# SDC_Latch_HS.net
KiCad netlist of a schematic drawn in Altium Designer
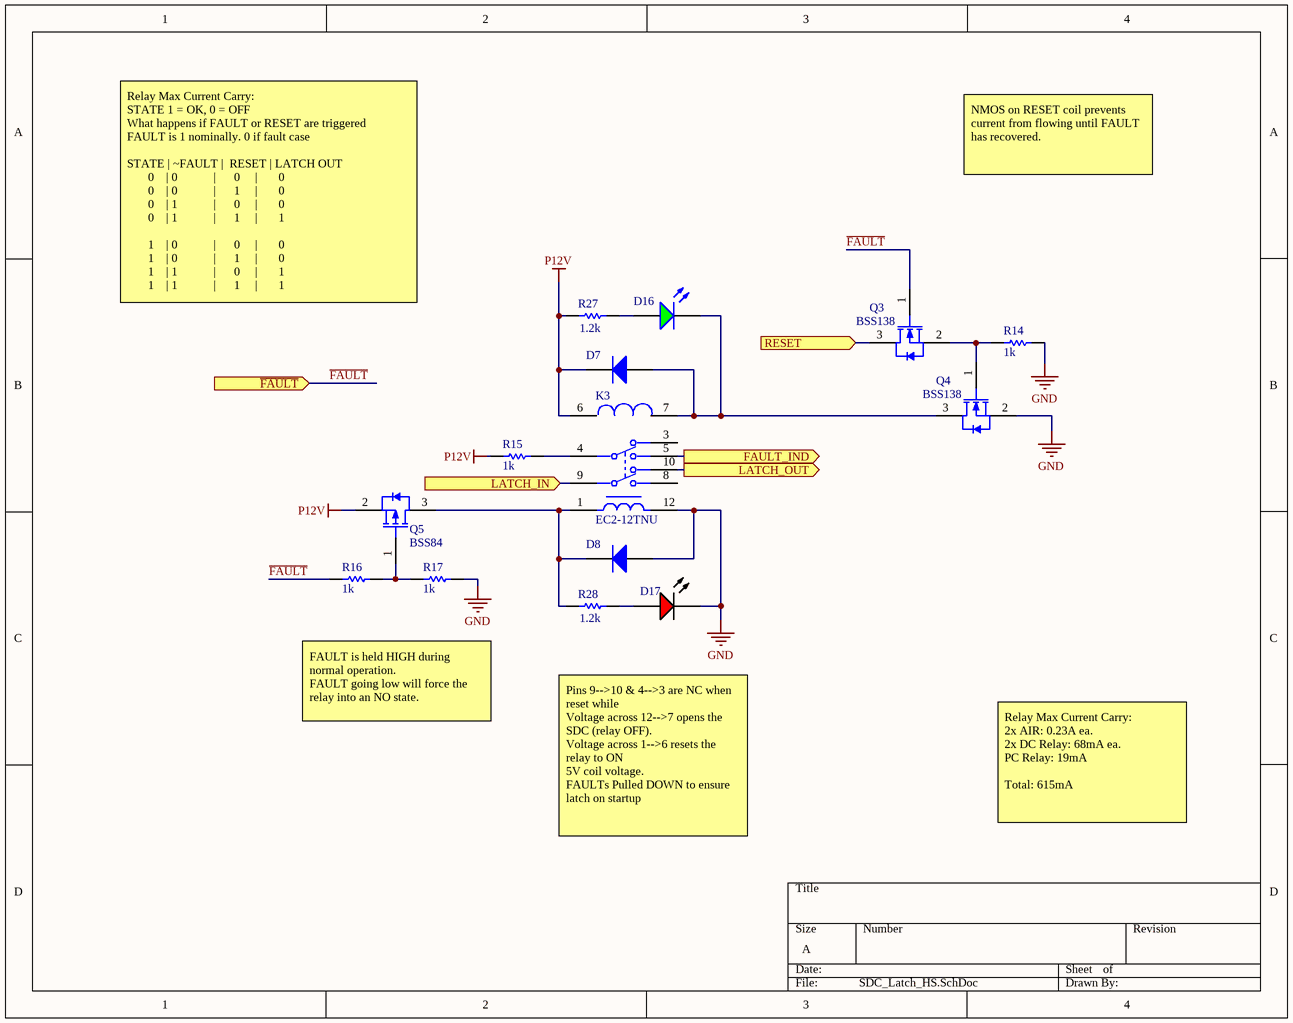
[diagram p0:  SDC_Latch_HS.SchDoc]

(export (version "E")
  (design (tool "Eeschema 10.0.6"))
  (components
    (comp (ref "D7")
      (value "Diode 1N4148")
      (footprint "DO-35")
      (description "High Conductance Fast Diode")
      (fields (field (name "PUBLISHER") "Altium Limited"))
      (libsource (lib "Miscellaneous Devices") (part "Diode 1N4148"))
    )
    (comp (ref "D8")
      (value "Diode 1N4148")
      (footprint "DO-35")
      (description "High Conductance Fast Diode")
      (fields (field (name "PUBLISHER") "Altium Limited"))
      (libsource (lib "Miscellaneous Devices") (part "Diode 1N4148"))
    )
    (comp (ref "D16")
      (value "597-3311-407F")
      (footprint "DIAL-597-3311-407F_V")
      (description "LED Green, 75 mW, 30 mA, -30 to 85 degC, 2-Pin SMD, RoHS, Tape and Reel")
      (fields (field (name "MANUFACTURER") "Dialight"))
      (libsource (lib "Altium Content Vault") (part "LED-GREEN-AK-2"))
    )
    (comp (ref "D17")
      (value "SML-LX1206IC-TR")
      (footprint "LUMX-SML-LX1206IC_V")
      (description "LED Red, 65 mW, -40 to 85 degC, 2-Pin SMD, RoHS, Tape and Reel")
      (fields (field (name "MANUFACTURER") "Lumex"))
      (libsource (lib "Altium Content Vault") (part "LED-RED-AK-2"))
    )
    (comp (ref "K3")
      (value "EC2-12TNU")
      (footprint "FP-EC2-12TNU-MFG")
      (description "RELAY GEN PURPOSE DPDT 2A 12VDC")
      (fields
        (field (name "MANUFACTURER") "KEMET")
        (field (name "OCTOPART") "https://octopart.com/ec2-12tnu-kemet-30529205")
      )
      (libsource (lib "Altium Content Vault") (part "a00bcedd7ab582def7fa3ba9be5e2d2"))
    )
    (comp (ref "Q3")
      (value "BSS138")
      (footprint "FAIR-SOT23-3_V")
      (fields (field (name "MANUFACTURER") "Fairchild") (field (name "POWER") "360mW"))
      (libsource (lib "University of California Riverside - FSAE") (part "NEMOS-GSD-3"))
    )
    (comp (ref "Q4")
      (value "BSS138")
      (footprint "FAIR-SOT23-3_V")
      (fields (field (name "MANUFACTURER") "Fairchild") (field (name "POWER") "360mW"))
      (libsource (lib "University of California Riverside - FSAE") (part "NEMOS-GSD-3"))
    )
    (comp (ref "Q5")
      (value "BSS84")
      (footprint "FAIR-SOT23-3_V")
      (fields (field (name "MANUFACTURER") "Fairchild") (field (name "POWER") "360mW"))
      (libsource (lib "University of California Riverside - FSAE") (part "PEMOS-GSD-3"))
    )
    (comp (ref "R14")
      (value "1k")
      (footprint "RESC3116X70X50ML13T20")
      (description "Chip Resistor, 1 KOhm, +/- 1%, 0.25 W, -55 to 155 degC, 1206 (3216 Metric)")
      (fields (field (name "POWER") "250mW") (field (name "TOLERANCE") "1%"))
      (libsource (lib "University of California Riverside - FSAE") (part "RES-2"))
    )
    (comp (ref "R15")
      (value "1k")
      (footprint "RESC3116X70X50ML13T20")
      (description "Chip Resistor, 1 KOhm, +/- 1%, 0.25 W, -55 to 155 degC, 1206 (3216 Metric)")
      (fields (field (name "POWER") "250mW") (field (name "TOLERANCE") "1%"))
      (libsource (lib "University of California Riverside - FSAE") (part "RES-2"))
    )
    (comp (ref "R16")
      (value "1k")
      (footprint "RESC3116X70X50ML13T20")
      (description "Chip Resistor, 1 KOhm, +/- 1%, 0.25 W, -55 to 155 degC, 1206 (3216 Metric)")
      (fields (field (name "POWER") "250mW") (field (name "TOLERANCE") "1%"))
      (libsource (lib "University of California Riverside - FSAE") (part "RES-2"))
    )
    (comp (ref "R17")
      (value "1k")
      (footprint "RESC3116X70X50ML13T20")
      (description "Chip Resistor, 1 KOhm, +/- 1%, 0.25 W, -55 to 155 degC, 1206 (3216 Metric)")
      (fields (field (name "POWER") "250mW") (field (name "TOLERANCE") "1%"))
      (libsource (lib "University of California Riverside - FSAE") (part "RES-2"))
    )
    (comp (ref "R27")
      (value "1.2k")
      (footprint "RESC3216X70X50LL05T20")
      (description "ERJ8ENF1201V")
      (fields (field (name "MANUFACTURER") "Panasonic"))
      (libsource (lib "Altium Content Vault") (part "RES"))
    )
    (comp (ref "R28")
      (value "1.2k")
      (footprint "RESC3216X70X50LL05T20")
      (description "ERJ8ENF1201V")
      (fields (field (name "MANUFACTURER") "Panasonic"))
      (libsource (lib "Altium Content Vault") (part "RES"))
    )
  )
  (nets
    (net (code "1") (name "/FAULT_IND") (class "Default")
      (node (ref "K3") (pin "5") (pinfunction "5_5") (pintype "passive"))
    )
    (net (code "2") (name "/LATCH_IN") (class "Default")
      (node (ref "K3") (pin "9") (pinfunction "9_9") (pintype "passive"))
    )
    (net (code "3") (name "/LATCH_OUT") (class "Default")
      (node (ref "K3") (pin "10") (pinfunction "10_10") (pintype "passive"))
    )
    (net (code "4") (name "/RESET") (class "Default")
      (node (ref "Q3") (pin "3") (pinfunction "D_3") (pintype "passive"))
    )
    (net (code "5") (name "/~{FAULT}") (class "Default")
      (node (ref "Q3") (pin "1") (pinfunction "G_1") (pintype "passive"))
      (node (ref "R16") (pin "2") (pinfunction "2_2") (pintype "passive"))
    )
    (net (code "6") (name "GND") (class "Default")
      (node (ref "D17") (pin "2") (pinfunction "K_2") (pintype "passive"))
      (node (ref "D8") (pin "1") (pinfunction "A_1") (pintype "passive"))
      (node (ref "K3") (pin "12") (pinfunction "SET-_12") (pintype "passive"))
      (node (ref "Q4") (pin "2") (pinfunction "S_2") (pintype "passive"))
      (node (ref "R14") (pin "1") (pinfunction "1_1") (pintype "passive"))
      (node (ref "R17") (pin "1") (pinfunction "1_1") (pintype "passive"))
    )
    (net (code "7") (name "Net-(D8-K)") (class "Default")
      (node (ref "D8") (pin "2") (pinfunction "K_2") (pintype "passive"))
      (node (ref "K3") (pin "1") (pinfunction "SET+_1") (pintype "passive"))
      (node (ref "Q5") (pin "3") (pinfunction "DRAIN_3") (pintype "passive"))
      (node (ref "R28") (pin "1") (pinfunction "1_1") (pintype "passive"))
    )
    (net (code "8") (name "Net-(D16-A)") (class "Default")
      (node (ref "D16") (pin "1") (pinfunction "A_1") (pintype "passive"))
      (node (ref "R27") (pin "2") (pinfunction "2_2") (pintype "passive"))
    )
    (net (code "9") (name "Net-(D16-K)") (class "Default")
      (node (ref "D16") (pin "2") (pinfunction "K_2") (pintype "passive"))
      (node (ref "D7") (pin "1") (pinfunction "A_1") (pintype "passive"))
      (node (ref "K3") (pin "7") (pinfunction "RESET-_7") (pintype "passive"))
      (node (ref "Q4") (pin "3") (pinfunction "D_3") (pintype "passive"))
    )
    (net (code "10") (name "Net-(D17-A)") (class "Default")
      (node (ref "D17") (pin "1") (pinfunction "A_1") (pintype "passive"))
      (node (ref "R28") (pin "2") (pinfunction "2_2") (pintype "passive"))
    )
    (net (code "11") (name "Net-(K3-Pad4)") (class "Default")
      (node (ref "K3") (pin "4") (pinfunction "4_4") (pintype "passive"))
      (node (ref "R15") (pin "1") (pinfunction "1_1") (pintype "passive"))
    )
    (net (code "12") (name "Net-(Q3-S)") (class "Default")
      (node (ref "Q3") (pin "2") (pinfunction "S_2") (pintype "passive"))
      (node (ref "Q4") (pin "1") (pinfunction "G_1") (pintype "passive"))
      (node (ref "R14") (pin "2") (pinfunction "2_2") (pintype "passive"))
    )
    (net (code "13") (name "Net-(Q5-GATE)") (class "Default")
      (node (ref "Q5") (pin "1") (pinfunction "GATE_1") (pintype "passive"))
      (node (ref "R16") (pin "1") (pinfunction "1_1") (pintype "passive"))
      (node (ref "R17") (pin "2") (pinfunction "2_2") (pintype "passive"))
    )
    (net (code "14") (name "P12V") (class "Default")
      (node (ref "D7") (pin "2") (pinfunction "K_2") (pintype "passive"))
      (node (ref "K3") (pin "6") (pinfunction "RESET+_6") (pintype "passive"))
      (node (ref "Q5") (pin "2") (pinfunction "SOURCE_2") (pintype "passive"))
      (node (ref "R15") (pin "2") (pinfunction "2_2") (pintype "passive"))
      (node (ref "R27") (pin "1") (pinfunction "1_1") (pintype "passive"))
    )
    (net (code "15") (name "unconnected-(K3-Pad3)") (class "Default")
      (node (ref "K3") (pin "3") (pinfunction "3_3") (pintype "passive"))
    )
    (net (code "16") (name "unconnected-(K3-Pad8)") (class "Default")
      (node (ref "K3") (pin "8") (pinfunction "8_8") (pintype "passive"))
    )
  )
)
